# DIGITALS.net
KiCad netlist of a schematic drawn in Altium Designer
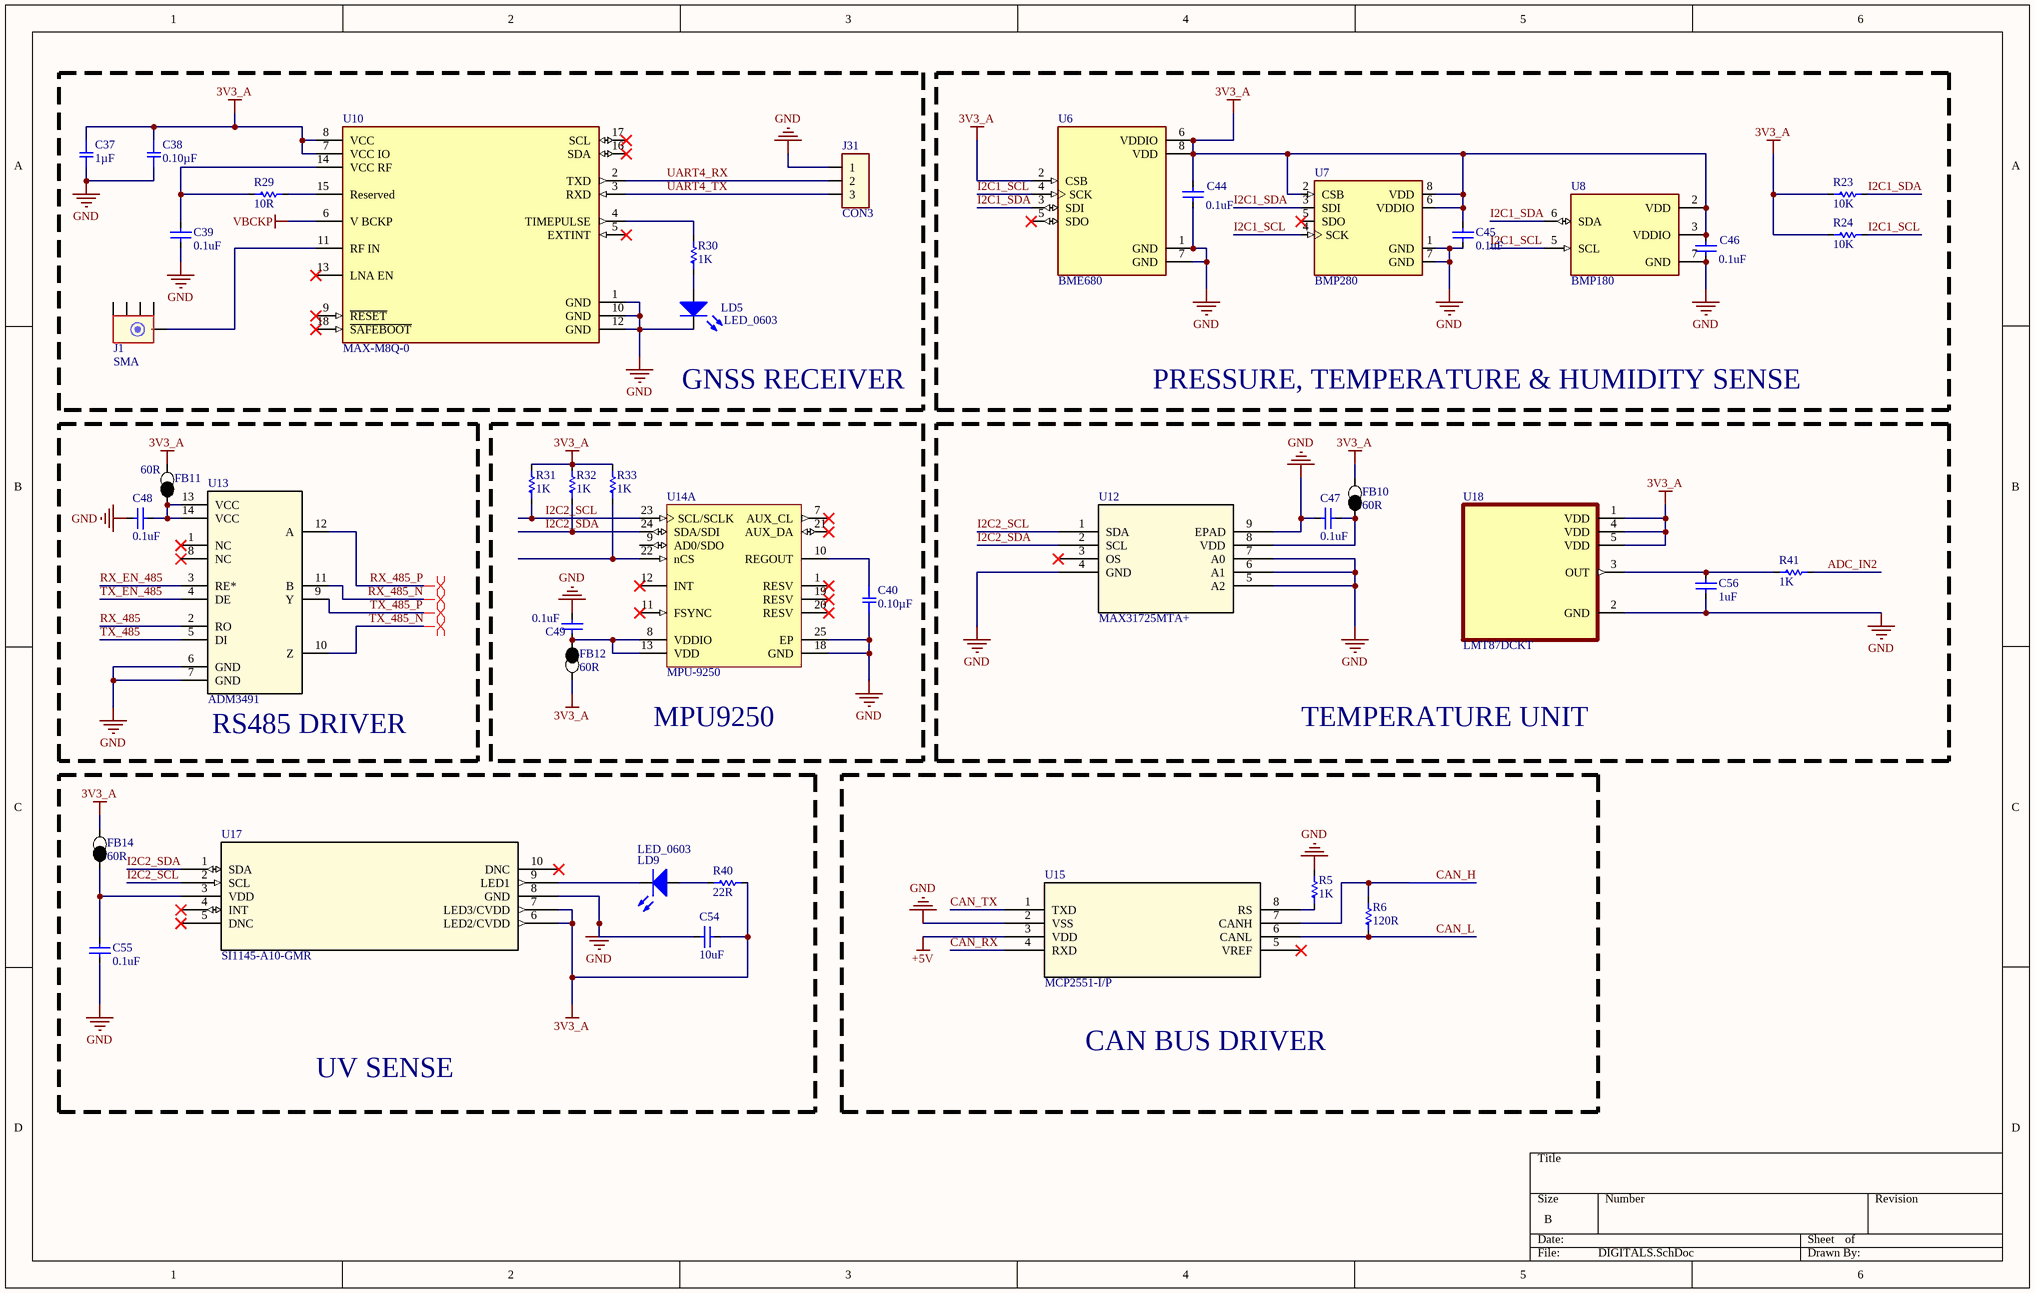
[diagram p0: DIGITALS.SchDoc]

(export (version "E")
  (design (tool "Eeschema 10.0.6"))
  (components
    (comp (ref "C37")
      (value "1µF")
      (footprint "SMD-0603C")
      (description "CAP CER 1UF 25V X5R 0603")
      (fields
        (field (name "DIGI-KEY PART NUMBER") "490-12321-1-ND")
        (field (name "PART NUMBER") "GRT188R61E105KE13D")
      )
      (libsource (lib "capacitor_murata_0603") (part "GRT188R61E105KE13D"))
    )
    (comp (ref "C38")
      (value "0.10µF")
      (footprint "SMD-0603C")
      (description "CAP CER 0.1UF 50V X7R 0603")
      (fields
        (field (name "DIGI-KEY PART NUMBER") "490-5798-1-ND")
        (field (name "PART NUMBER") "GCJ188R71H104KA12D")
      )
      (libsource (lib "capacitor_murata_0603") (part "GCJ188R71H104KA12D"))
    )
    (comp (ref "C39")
      (value "0.1uF")
      (footprint "CAPC1608-0603X90N")
      (description "CAP CER 0.1UF 50V X7R 0603")
      (fields (field (name "MANUFACTURER") "Samsung Electro-Mechanics") (field (name "VOLTAGE") "50V"))
      (libsource (lib "ANTSIS_PASSIVE") (part "CAP 0.1uF"))
    )
    (comp (ref "C40")
      (value "0.10µF")
      (footprint "SMD-0603C")
      (description "CAP CER 0.1UF 16V X7R 0603")
      (fields
        (field (name "DIGI-KEY PART NUMBER") "490-5796-1-ND")
        (field (name "PART NUMBER") "GCJ188R71C104KA01D")
      )
      (libsource (lib "capacitor_murata_0603") (part "GCJ188R71C104KA01D"))
    )
    (comp (ref "C44")
      (value "0.1uF")
      (footprint "CAPC1608-0603X90N")
      (description "CAP CER 0.1UF 50V X7R 0603")
      (fields (field (name "MANUFACTURER") "Samsung Electro-Mechanics") (field (name "VOLTAGE") "50V"))
      (libsource (lib "ANTSIS_PASSIVE") (part "CAP 0.1uF"))
    )
    (comp (ref "C45")
      (value "0.1uF")
      (footprint "CAPC1608-0603X90N")
      (description "CAP CER 0.1UF 50V X7R 0603")
      (fields (field (name "MANUFACTURER") "Samsung Electro-Mechanics") (field (name "VOLTAGE") "50V"))
      (libsource (lib "ANTSIS_PASSIVE") (part "CAP 0.1uF"))
    )
    (comp (ref "C46")
      (value "0.1uF")
      (footprint "CAPC1608-0603X90N")
      (description "CAP CER 0.1UF 50V X7R 0603")
      (fields (field (name "MANUFACTURER") "Samsung Electro-Mechanics") (field (name "VOLTAGE") "50V"))
      (libsource (lib "ANTSIS_PASSIVE") (part "CAP 0.1uF"))
    )
    (comp (ref "C47")
      (value "0.1uF")
      (footprint "CAPC1608-0603X90N")
      (description "CAP CER 0.1UF 50V X7R 0603")
      (fields (field (name "MANUFACTURER") "Samsung Electro-Mechanics") (field (name "VOLTAGE") "50V"))
      (libsource (lib "ANTSIS_PASSIVE") (part "CAP 0.1uF"))
    )
    (comp (ref "C48")
      (value "0.1uF")
      (footprint "CAPC1608-0603X90N")
      (description "CAP CER 0.1UF 50V X7R 0603")
      (fields (field (name "MANUFACTURER") "Samsung Electro-Mechanics") (field (name "VOLTAGE") "50V"))
      (libsource (lib "ANTSIS_PASSIVE") (part "CAP 0.1uF"))
    )
    (comp (ref "C49")
      (value "0.1uF")
      (footprint "CAPC1608-0603X90N")
      (description "CAP CER 0.1UF 50V X7R 0603")
      (fields (field (name "MANUFACTURER") "Samsung Electro-Mechanics") (field (name "VOLTAGE") "50V"))
      (libsource (lib "ANTSIS_PASSIVE") (part "CAP 0.1uF"))
    )
    (comp (ref "C54")
      (value "10uF")
      (footprint "CAPC1608-0603X90N")
      (description "CAP CER 10UF 10V X5R 0603")
      (fields (field (name "MANUFACTURER") "Samsung Electro-Mechanics") (field (name "VOLTAGE") "10V"))
      (libsource (lib "ANTSIS_PASSIVE") (part "CAP 10uF"))
    )
    (comp (ref "C55")
      (value "0.1uF")
      (footprint "CAPC1608-0603X90N")
      (description "CAP CER 0.1UF 50V X7R 0603")
      (fields (field (name "MANUFACTURER") "Samsung Electro-Mechanics") (field (name "VOLTAGE") "50V"))
      (libsource (lib "ANTSIS_PASSIVE") (part "CAP 0.1uF"))
    )
    (comp (ref "C56")
      (value "1uF")
      (footprint "CAPC1608-0603X90N")
      (description "CAP CER 1UF 25V X7R 0603")
      (fields (field (name "MANUFACTURER") "Samsung Electro-Mechanics") (field (name "VOLTAGE") "25V"))
      (libsource (lib "ANTSIS_PASSIVE") (part "CAP 1uF"))
    )
    (comp (ref "FB10")
      (value "60R")
      (footprint "INDC1608-0603X80N")
      (description "FERRITE BEAD 60 OHM 0603 1LN")
      (fields (field (name "MANUFACTURER") "Würth Elektronik") (field (name "TOLERANCE") "-55°C ~ 125°C"))
      (libsource (lib "ANTSIS_PASSIVE") (part "FERRITE 60R 3A"))
    )
    (comp (ref "FB11")
      (value "60R")
      (footprint "INDC1608-0603X80N")
      (description "FERRITE BEAD 60 OHM 0603 1LN")
      (fields (field (name "MANUFACTURER") "Würth Elektronik") (field (name "TOLERANCE") "-55°C ~ 125°C"))
      (libsource (lib "ANTSIS_PASSIVE") (part "FERRITE 60R 3A"))
    )
    (comp (ref "FB12")
      (value "60R")
      (footprint "INDC1608-0603X80N")
      (description "FERRITE BEAD 60 OHM 0603 1LN")
      (fields (field (name "MANUFACTURER") "Würth Elektronik") (field (name "TOLERANCE") "-55°C ~ 125°C"))
      (libsource (lib "ANTSIS_PASSIVE") (part "FERRITE 60R 3A"))
    )
    (comp (ref "FB14")
      (value "60R")
      (footprint "INDC1608-0603X80N")
      (description "FERRITE BEAD 60 OHM 0603 1LN")
      (fields (field (name "MANUFACTURER") "Würth Elektronik") (field (name "TOLERANCE") "-55°C ~ 125°C"))
      (libsource (lib "ANTSIS_PASSIVE") (part "FERRITE 60R 3A"))
    )
    (comp (ref "J1")
      (value "SMA")
      (footprint "HUBER-SUHNER_85 SMA-50-0-101/111 NE")
      (libsource (lib "ANTSIS_CONNECTORS") (part "SMA"))
    )
    (comp (ref "J31")
      (value "CON3")
      (footprint "HDR1X3M")
      (libsource (lib "ANTSIS_CONNECTORS") (part "CON3"))
    )
    (comp (ref "LD5")
      (value "LED_0603")
      (footprint "LED0603-1608X55N-GREEN")
      (description "LED GREEN CLEAR CHIP SMD")
      (fields (field (name "MANUFACTURER") "Lite-On Inc.") (field (name "VOLTAGE") "2.1V"))
      (libsource (lib "ANTSIS_DIODE_TRANSISTOR") (part "LED_0603"))
    )
    (comp (ref "LD9")
      (value "LED_0603")
      (footprint "LED0603-1608X55N-GREEN")
      (description "LED GREEN CLEAR CHIP SMD")
      (fields (field (name "MANUFACTURER") "Lite-On Inc.") (field (name "VOLTAGE") "2.1V"))
      (libsource (lib "ANTSIS_DIODE_TRANSISTOR") (part "LED_0603"))
    )
    (comp (ref "R5")
      (value "1K")
      (footprint "RESC1608-0603X50N")
      (description "RES SMD 10K OHM 1% 1/10W 0603")
      (fields (field (name "MANUFACTURER") "Yageo"))
      (libsource (lib "ANTSIS_PASSIVE") (part "RESISTOR 10K"))
    )
    (comp (ref "R6")
      (value "120R")
      (footprint "RESC1608-0603X50N")
      (description "RES SMD 0 OHM JUMPER 1/10W 0603")
      (fields (field (name "MANUFACTURER") "Yageo"))
      (libsource (lib "ANTSIS_PASSIVE") (part "RESISTOR 0R"))
    )
    (comp (ref "R23")
      (value "10K")
      (footprint "RESC1608-0603X50N")
      (description "RES SMD 10K OHM 1% 1/10W 0603")
      (fields (field (name "MANUFACTURER") "Yageo"))
      (libsource (lib "ANTSIS_PASSIVE") (part "RESISTOR 10K"))
    )
    (comp (ref "R24")
      (value "10K")
      (footprint "RESC1608-0603X50N")
      (description "RES SMD 10K OHM 1% 1/10W 0603")
      (fields (field (name "MANUFACTURER") "Yageo"))
      (libsource (lib "ANTSIS_PASSIVE") (part "RESISTOR 10K"))
    )
    (comp (ref "R29")
      (value "10R")
      (footprint "RESC1608-0603X50N")
      (description "RES SMD 10 OHM 1% 1/10W 0603")
      (fields (field (name "MANUFACTURER") "Yageo"))
      (libsource (lib "ANTSIS_PASSIVE") (part "RESISTOR 10K"))
    )
    (comp (ref "R30")
      (value "1K")
      (footprint "RESC1608-0603X50N")
      (description "RES SMD 1K OHM 1% 1/10W 0603")
      (fields (field (name "MANUFACTURER") "Yageo"))
      (libsource (lib "ANTSIS_PASSIVE") (part "RESISTOR 1K"))
    )
    (comp (ref "R31")
      (value "1K")
      (footprint "RESC1608-0603X50N")
      (description "RES SMD 1K OHM 1% 1/10W 0603")
      (fields (field (name "MANUFACTURER") "Yageo"))
      (libsource (lib "ANTSIS_PASSIVE") (part "RESISTOR 1K"))
    )
    (comp (ref "R32")
      (value "1K")
      (footprint "RESC1608-0603X50N")
      (description "RES SMD 1K OHM 1% 1/10W 0603")
      (fields (field (name "MANUFACTURER") "Yageo"))
      (libsource (lib "ANTSIS_PASSIVE") (part "RESISTOR 1K"))
    )
    (comp (ref "R33")
      (value "1K")
      (footprint "RESC1608-0603X50N")
      (description "RES SMD 1K OHM 1% 1/10W 0603")
      (fields (field (name "MANUFACTURER") "Yageo"))
      (libsource (lib "ANTSIS_PASSIVE") (part "RESISTOR 1K"))
    )
    (comp (ref "R40")
      (value "22R")
      (footprint "RESC1608-0603X50N")
      (description "RES 22 OHM 5% 1/10W 0603")
      (fields (field (name "MANUFACTURER") "Stackpole Electronics Inc") (field (name "TOLERANCE") "5%"))
      (libsource (lib "ANTSIS_PASSIVE") (part "RESISTOR 22R"))
    )
    (comp (ref "R41")
      (value "1K")
      (footprint "RESC1608-0603X50N")
      (description "RES SMD 1K OHM 1% 1/10W 0603")
      (fields (field (name "MANUFACTURER") "Yageo"))
      (libsource (lib "ANTSIS_PASSIVE") (part "RESISTOR 1K"))
    )
    (comp (ref "U6")
      (value "BME680")
      (footprint "PSON80P300X300X100-8N")
      (description "Gas, Humidity, Pressure, Temperature Sensor IÂ²C, SPI Output")
      (fields (field (name "MF") "Bosch Sensortec"))
      (libsource (lib "BME680") (part "BME680"))
    )
    (comp (ref "U7")
      (value "BMP280")
      (footprint "XDCR_BMP280")
      (description "Pressure Sensor 4.35PSI ~ 15.95PSI _30kPa ~ 110kPa_ Absolute 16b 8-SMD")
      (fields (field (name "DIGI-KEY_PART_NUMBER") "828-1064-1-ND") (field (name "MF") "Bosch"))
      (libsource (lib "BMP280") (part "BMP280"))
    )
    (comp (ref "U8")
      (value "BMP180")
      (footprint "BMP180")
      (description "Pressure Sensor 4.35PSI ~ 15.95PSI _30kPa ~ 110kPa_ Absolute 16 ~ 19 b 7-VLGA")
      (fields (field (name "MF") "Bosch Sensortec") (field (name "DIGI-KEY_PART_NUMBER") "828-1027-1-ND"))
      (libsource (lib "BMP180") (part "BMP180"))
    )
    (comp (ref "U10")
      (value "MAX-M8Q-0")
      (footprint "FP-MAX-M8Q-0-MFG")
      (description "RF RCVR GNSS/GPS 1.575GHZ 18LCC")
      (libsource (lib "Altium Content Vault") (part "3a4eaf80b39255b10f8ea21395ff7da"))
    )
    (comp (ref "U12")
      (value "MAX31725MTA+")
      (footprint "SON65P300X300X80-9N")
      (description "No Description Available")
      (fields (field (name "COPYRIGHT") "Copyright (C) 2021 Ultra Librarian. All rights reserved."))
      (libsource (lib "MAX31725MTA&plus_") (part "MAX31725MTA+"))
    )
    (comp (ref "U13")
      (value "ADM3491")
      (footprint "SOIC127P600-14N")
      (description "1/1 Transceiver Full RS422, RS485 14-SOIC")
      (fields (field (name "MANUFACTURER") "Analog Devices Inc.") (field (name "VOLTAGE") "3V ~ 3.6V"))
      (libsource (lib "ANTSIS") (part "ADM3491"))
    )
    (comp (ref "U14")
      (value "MPU-9250")
      (footprint "INSE-QFN-24-1700X1540TP_N")
      (description "9-axis MotionTracking device, 2.4 to 3,6 V, -40 to 85 degC, 24-Pin QFN, RoHS, Tape and Reel")
      (fields (field (name "MANUFACTURER") "InvenSense"))
      (libsource (lib "Altium Content Vault") (part "INSE-MPU-9250-QFN-24"))
    )
    (comp (ref "U15")
      (value "MCP2551-I/P")
      (footprint "PDIP8_300MC_MCH")
      (description "No Description Available")
      (fields (field (name "COPYRIGHT") "Copyright (C) 2021 Ultra Librarian. All rights reserved."))
      (libsource (lib "MCP2551-I&slash_P") (part "MCP2551-I/P"))
    )
    (comp (ref "U17")
      (value "SI1145-A10-GMR")
      (footprint "QFN10_2X2_SIL")
      (description "No Description Available")
      (fields (field (name "COPYRIGHT") "Copyright (C) 2021 Ultra Librarian. All rights reserved."))
      (libsource (lib "SI1145-A10-GMR") (part "SI1145-A10-GMR"))
    )
    (comp (ref "U18")
      (value "LMT87DCKT")
      (footprint "SOT65P210X110-5N")
      (description "2C 2.7V to 5.5V analog output temperature sensor with -13.6 mV/C gain 5-SC70 -50 to 150")
      (fields (field (name "MF") "Texas Instruments"))
      (libsource (lib "LMT87DCKT") (part "LMT87DCKT"))
    )
  )
  (nets
    (net (code "1") (name "+5V") (class "Default")
      (node (ref "U15") (pin "3") (pinfunction "VDD_3") (pintype "passive"))
    )
    (net (code "2") (name "/ADC_IN2") (class "Default")
      (node (ref "R41") (pin "2") (pinfunction "2_2") (pintype "passive"))
    )
    (net (code "3") (name "/CAN_H") (class "Default")
      (node (ref "R6") (pin "2") (pinfunction "2_2") (pintype "passive"))
      (node (ref "U15") (pin "7") (pinfunction "CANH_7") (pintype "passive"))
    )
    (net (code "4") (name "/CAN_L") (class "Default")
      (node (ref "R6") (pin "1") (pinfunction "1_1") (pintype "passive"))
      (node (ref "U15") (pin "6") (pinfunction "CANL_6") (pintype "passive"))
    )
    (net (code "5") (name "/CAN_RX") (class "Default")
      (node (ref "U15") (pin "4") (pinfunction "RXD_4") (pintype "passive"))
    )
    (net (code "6") (name "/CAN_TX") (class "Default")
      (node (ref "U15") (pin "1") (pinfunction "TXD_1") (pintype "passive"))
    )
    (net (code "7") (name "/I2C1_SCL") (class "Default")
      (node (ref "R24") (pin "2") (pinfunction "2_2") (pintype "passive"))
      (node (ref "U6") (pin "4") (pinfunction "SCK_4") (pintype "input"))
      (node (ref "U7") (pin "4") (pinfunction "SCK_4") (pintype "input"))
      (node (ref "U8") (pin "5") (pinfunction "SCL_5") (pintype "input"))
    )
    (net (code "8") (name "/I2C1_SDA") (class "Default")
      (node (ref "R23") (pin "2") (pinfunction "2_2") (pintype "passive"))
      (node (ref "U6") (pin "3") (pinfunction "SDI_3") (pintype "bidirectional"))
      (node (ref "U7") (pin "3") (pinfunction "SDI_3") (pintype "bidirectional"))
      (node (ref "U8") (pin "6") (pinfunction "SDA_6") (pintype "bidirectional"))
    )
    (net (code "9") (name "/I2C2_SCL") (class "Default")
      (node (ref "R31") (pin "1") (pinfunction "1_1") (pintype "passive"))
      (node (ref "U12") (pin "1") (pinfunction "SDA_1") (pintype "passive"))
      (node (ref "U14") (pin "23") (pinfunction "SCL/SCLK_23") (pintype "input"))
      (node (ref "U17") (pin "2") (pinfunction "SCL_2") (pintype "input"))
    )
    (net (code "10") (name "/I2C2_SDA") (class "Default")
      (node (ref "R32") (pin "1") (pinfunction "1_1") (pintype "passive"))
      (node (ref "U12") (pin "2") (pinfunction "SCL_2") (pintype "passive"))
      (node (ref "U14") (pin "24") (pinfunction "SDA/SDI_24") (pintype "bidirectional"))
      (node (ref "U17") (pin "1") (pinfunction "SDA_1") (pintype "bidirectional"))
    )
    (net (code "11") (name "/RX_485") (class "Default")
      (node (ref "U13") (pin "2") (pinfunction "RO_2") (pintype "passive"))
    )
    (net (code "12") (name "/RX_485_N") (class "Default")
      (node (ref "U13") (pin "11") (pinfunction "B_11") (pintype "passive"))
    )
    (net (code "13") (name "/RX_485_P") (class "Default")
      (node (ref "U13") (pin "12") (pinfunction "A_12") (pintype "passive"))
    )
    (net (code "14") (name "/RX_EN_485") (class "Default")
      (node (ref "U13") (pin "3") (pinfunction "RE*_3") (pintype "passive"))
    )
    (net (code "15") (name "/TX_485") (class "Default")
      (node (ref "U13") (pin "5") (pinfunction "DI_5") (pintype "passive"))
    )
    (net (code "16") (name "/TX_485_N") (class "Default")
      (node (ref "U13") (pin "10") (pinfunction "Z_10") (pintype "passive"))
    )
    (net (code "17") (name "/TX_485_P") (class "Default")
      (node (ref "U13") (pin "9") (pinfunction "Y_9") (pintype "passive"))
    )
    (net (code "18") (name "/TX_EN_485") (class "Default")
      (node (ref "U13") (pin "4") (pinfunction "DE_4") (pintype "passive"))
    )
    (net (code "19") (name "/UART4_RX") (class "Default")
      (node (ref "J31") (pin "2") (pinfunction "2_2") (pintype "passive"))
      (node (ref "U10") (pin "2") (pinfunction "TXD_2") (pintype "output"))
    )
    (net (code "20") (name "/UART4_TX") (class "Default")
      (node (ref "J31") (pin "3") (pinfunction "3_3") (pintype "passive"))
      (node (ref "U10") (pin "3") (pinfunction "RXD_3") (pintype "input"))
    )
    (net (code "21") (name "3V3_A") (class "Default")
      (node (ref "C37") (pin "1") (pinfunction "1_1") (pintype "passive"))
      (node (ref "C38") (pin "1") (pinfunction "1_1") (pintype "passive"))
      (node (ref "C44") (pin "2") (pinfunction "2_2") (pintype "passive"))
      (node (ref "C45") (pin "2") (pinfunction "2_2") (pintype "passive"))
      (node (ref "C46") (pin "2") (pinfunction "2_2") (pintype "passive"))
      (node (ref "C54") (pin "1") (pinfunction "1_1") (pintype "passive"))
      (node (ref "FB10") (pin "2") (pinfunction "2_2") (pintype "passive"))
      (node (ref "FB11") (pin "2") (pinfunction "2_2") (pintype "passive"))
      (node (ref "FB12") (pin "2") (pinfunction "2_2") (pintype "passive"))
      (node (ref "FB14") (pin "2") (pinfunction "2_2") (pintype "passive"))
      (node (ref "R23") (pin "1") (pinfunction "1_1") (pintype "passive"))
      (node (ref "R24") (pin "1") (pinfunction "1_1") (pintype "passive"))
      (node (ref "R31") (pin "2") (pinfunction "2_2") (pintype "passive"))
      (node (ref "R32") (pin "2") (pinfunction "2_2") (pintype "passive"))
      (node (ref "R33") (pin "2") (pinfunction "2_2") (pintype "passive"))
      (node (ref "R40") (pin "2") (pinfunction "2_2") (pintype "passive"))
      (node (ref "U10") (pin "7") (pinfunction "VCC_IO_7") (pintype "power_in"))
      (node (ref "U10") (pin "8") (pinfunction "VCC_8") (pintype "power_in"))
      (node (ref "U17") (pin "6") (pinfunction "LED2/CVDD_6") (pintype "output"))
      (node (ref "U17") (pin "7") (pinfunction "LED3/CVDD_7") (pintype "output"))
      (node (ref "U18") (pin "1") (pinfunction "VDD_1") (pintype "power_in"))
      (node (ref "U18") (pin "4") (pinfunction "VDD_4") (pintype "power_in"))
      (node (ref "U18") (pin "5") (pinfunction "VDD_5") (pintype "power_in"))
      (node (ref "U6") (pin "2") (pinfunction "CSB_2") (pintype "input"))
      (node (ref "U6") (pin "6") (pinfunction "VDDIO_6") (pintype "power_in"))
      (node (ref "U6") (pin "8") (pinfunction "VDD_8") (pintype "power_in"))
      (node (ref "U7") (pin "2") (pinfunction "CSB_2") (pintype "input"))
      (node (ref "U7") (pin "6") (pinfunction "VDDIO_6") (pintype "power_in"))
      (node (ref "U7") (pin "8") (pinfunction "VDD_8") (pintype "power_in"))
      (node (ref "U8") (pin "2") (pinfunction "VDD_2") (pintype "power_in"))
      (node (ref "U8") (pin "3") (pinfunction "VDDIO_3") (pintype "power_in"))
    )
    (net (code "22") (name "GND") (class "Default")
      (node (ref "C37") (pin "2") (pinfunction "2_2") (pintype "passive"))
      (node (ref "C38") (pin "2") (pinfunction "2_2") (pintype "passive"))
      (node (ref "C39") (pin "1") (pinfunction "1_1") (pintype "passive"))
      (node (ref "C40") (pin "2") (pinfunction "2_2") (pintype "passive"))
      (node (ref "C44") (pin "1") (pinfunction "1_1") (pintype "passive"))
      (node (ref "C45") (pin "1") (pinfunction "1_1") (pintype "passive"))
      (node (ref "C46") (pin "1") (pinfunction "1_1") (pintype "passive"))
      (node (ref "C47") (pin "2") (pinfunction "2_2") (pintype "passive"))
      (node (ref "C48") (pin "1") (pinfunction "1_1") (pintype "passive"))
      (node (ref "C49") (pin "2") (pinfunction "2_2") (pintype "passive"))
      (node (ref "C54") (pin "2") (pinfunction "2_2") (pintype "passive"))
      (node (ref "C55") (pin "2") (pinfunction "2_2") (pintype "passive"))
      (node (ref "C56") (pin "1") (pinfunction "1_1") (pintype "passive"))
      (node (ref "J31") (pin "1") (pinfunction "1_1") (pintype "passive"))
      (node (ref "LD5") (pin "2") (pinfunction "K_2") (pintype "passive"))
      (node (ref "R5") (pin "2") (pinfunction "2_2") (pintype "passive"))
      (node (ref "U10") (pin "1") (pinfunction "GND_1") (pintype "power_in"))
      (node (ref "U10") (pin "10") (pinfunction "GND_10") (pintype "power_in"))
      (node (ref "U10") (pin "12") (pinfunction "GND_12") (pintype "power_in"))
      (node (ref "U12") (pin "4") (pinfunction "GND_4") (pintype "power_in"))
      (node (ref "U12") (pin "5") (pinfunction "A2_5") (pintype "passive"))
      (node (ref "U12") (pin "6") (pinfunction "A1_6") (pintype "passive"))
      (node (ref "U12") (pin "7") (pinfunction "A0_7") (pintype "passive"))
      (node (ref "U12") (pin "9") (pinfunction "EPAD_9") (pintype "power_in"))
      (node (ref "U13") (pin "6") (pinfunction "GND_6") (pintype "power_in"))
      (node (ref "U13") (pin "7") (pinfunction "GND_7") (pintype "power_in"))
      (node (ref "U14") (pin "18") (pinfunction "GND_18") (pintype "power_in"))
      (node (ref "U14") (pin "25") (pinfunction "EP_25") (pintype "passive"))
      (node (ref "U15") (pin "2") (pinfunction "VSS_2") (pintype "passive"))
      (node (ref "U17") (pin "8") (pinfunction "GND_8") (pintype "power_in"))
      (node (ref "U18") (pin "2") (pinfunction "GND_2") (pintype "power_in"))
      (node (ref "U6") (pin "1") (pinfunction "GND_1") (pintype "power_in"))
      (node (ref "U6") (pin "7") (pinfunction "GND_7") (pintype "power_in"))
      (node (ref "U7") (pin "1") (pinfunction "GND_1") (pintype "power_in"))
      (node (ref "U7") (pin "7") (pinfunction "GND_7") (pintype "power_in"))
      (node (ref "U8") (pin "7") (pinfunction "GND_7") (pintype "power_in"))
    )
    (net (code "23") (name "Net-(C48-Pad2)") (class "Default")
      (node (ref "C48") (pin "2") (pinfunction "2_2") (pintype "passive"))
      (node (ref "FB11") (pin "1") (pinfunction "1_1") (pintype "passive"))
      (node (ref "U13") (pin "13") (pinfunction "VCC_13") (pintype "power_in"))
      (node (ref "U13") (pin "14") (pinfunction "VCC_14") (pintype "power_in"))
    )
    (net (code "24") (name "Net-(LD5-A)") (class "Default")
      (node (ref "LD5") (pin "1") (pinfunction "A_1") (pintype "passive"))
      (node (ref "R30") (pin "1") (pinfunction "1_1") (pintype "passive"))
    )
    (net (code "25") (name "Net-(LD9-A)") (class "Default")
      (node (ref "LD9") (pin "1") (pinfunction "A_1") (pintype "passive"))
      (node (ref "R40") (pin "1") (pinfunction "1_1") (pintype "passive"))
    )
    (net (code "26") (name "Net-(LD9-K)") (class "Default")
      (node (ref "LD9") (pin "2") (pinfunction "K_2") (pintype "passive"))
      (node (ref "U17") (pin "9") (pinfunction "LED1_9") (pintype "output"))
    )
    (net (code "27") (name "Net-(U10-RF_IN)") (class "Default")
      (node (ref "J1") (pin "1") (pintype "passive"))
      (node (ref "U10") (pin "11") (pinfunction "RF_IN_11") (pintype "passive"))
    )
    (net (code "28") (name "Net-(U10-Reserved)") (class "Default")
      (node (ref "R29") (pin "2") (pinfunction "2_2") (pintype "passive"))
      (node (ref "U10") (pin "15") (pinfunction "Reserved_15") (pintype "passive"))
    )
    (net (code "29") (name "Net-(U10-TIMEPULSE)") (class "Default")
      (node (ref "R30") (pin "2") (pinfunction "2_2") (pintype "passive"))
      (node (ref "U10") (pin "4") (pinfunction "TIMEPULSE_4") (pintype "output"))
    )
    (net (code "30") (name "Net-(U10-VCC_RF)") (class "Default")
      (node (ref "C39") (pin "2") (pinfunction "2_2") (pintype "passive"))
      (node (ref "R29") (pin "1") (pinfunction "1_1") (pintype "passive"))
      (node (ref "U10") (pin "14") (pinfunction "VCC_RF_14") (pintype "power_in"))
    )
    (net (code "31") (name "Net-(U12-VDD)") (class "Default")
      (node (ref "C47") (pin "1") (pinfunction "1_1") (pintype "passive"))
      (node (ref "FB10") (pin "1") (pinfunction "1_1") (pintype "passive"))
      (node (ref "U12") (pin "8") (pinfunction "VDD_8") (pintype "power_in"))
    )
    (net (code "32") (name "Net-(U14A-REGOUT)") (class "Default")
      (node (ref "C40") (pin "1") (pinfunction "1_1") (pintype "passive"))
      (node (ref "U14") (pin "10") (pinfunction "REGOUT_10") (pintype "passive"))
    )
    (net (code "33") (name "Net-(U14A-VDD)") (class "Default")
      (node (ref "C49") (pin "1") (pinfunction "1_1") (pintype "passive"))
      (node (ref "FB12") (pin "1") (pinfunction "1_1") (pintype "passive"))
      (node (ref "U14") (pin "13") (pinfunction "VDD_13") (pintype "power_in"))
      (node (ref "U14") (pin "8") (pinfunction "VDDIO_8") (pintype "power_in"))
    )
    (net (code "34") (name "Net-(U14A-nCS)") (class "Default")
      (node (ref "R33") (pin "1") (pinfunction "1_1") (pintype "passive"))
      (node (ref "U14") (pin "22") (pinfunction "nCS_22") (pintype "input"))
    )
    (net (code "35") (name "Net-(U15-RS)") (class "Default")
      (node (ref "R5") (pin "1") (pinfunction "1_1") (pintype "passive"))
      (node (ref "U15") (pin "8") (pinfunction "RS_8") (pintype "passive"))
    )
    (net (code "36") (name "Net-(U17-VDD)") (class "Default")
      (node (ref "C55") (pin "1") (pinfunction "1_1") (pintype "passive"))
      (node (ref "FB14") (pin "1") (pinfunction "1_1") (pintype "passive"))
      (node (ref "U17") (pin "3") (pinfunction "VDD_3") (pintype "power_in"))
    )
    (net (code "37") (name "Net-(U18-OUT)") (class "Default")
      (node (ref "C56") (pin "2") (pinfunction "2_2") (pintype "passive"))
      (node (ref "R41") (pin "1") (pinfunction "1_1") (pintype "passive"))
      (node (ref "U18") (pin "3") (pinfunction "OUT_3") (pintype "output"))
    )
    (net (code "38") (name "VBCKP") (class "Default")
      (node (ref "U10") (pin "6") (pinfunction "V_BCKP_6") (pintype "power_in"))
    )
    (net (code "39") (name "unconnected-(J1-Pad2)") (class "Default")
      (node (ref "J1") (pin "2") (pintype "passive"))
    )
    (net (code "40") (name "unconnected-(J1-Pad3)") (class "Default")
      (node (ref "J1") (pin "3") (pintype "passive"))
    )
    (net (code "41") (name "unconnected-(J1-Pad4)") (class "Default")
      (node (ref "J1") (pin "4") (pintype "passive"))
    )
    (net (code "42") (name "unconnected-(J1-Pad5)") (class "Default")
      (node (ref "J1") (pin "5") (pintype "passive"))
    )
    (net (code "43") (name "unconnected-(U6-SDO-Pad5)") (class "Default")
      (node (ref "U6") (pin "5") (pinfunction "SDO_5") (pintype "bidirectional+no_connect"))
    )
    (net (code "44") (name "unconnected-(U7-SDO-Pad5)") (class "Default")
      (node (ref "U7") (pin "5") (pinfunction "SDO_5") (pintype "bidirectional+no_connect"))
    )
    (net (code "45") (name "unconnected-(U10-EXTINT-Pad5)") (class "Default")
      (node (ref "U10") (pin "5") (pinfunction "EXTINT_5") (pintype "input+no_connect"))
    )
    (net (code "46") (name "unconnected-(U10-LNA_EN-Pad13)") (class "Default")
      (node (ref "U10") (pin "13") (pinfunction "LNA_EN_13") (pintype "passive+no_connect"))
    )
    (net (code "47") (name "unconnected-(U10-SCL-Pad17)") (class "Default")
      (node (ref "U10") (pin "17") (pinfunction "SCL_17") (pintype "bidirectional+no_connect"))
    )
    (net (code "48") (name "unconnected-(U10-SDA-Pad16)") (class "Default")
      (node (ref "U10") (pin "16") (pinfunction "SDA_16") (pintype "bidirectional+no_connect"))
    )
    (net (code "49") (name "unconnected-(U10-~{RESET}-Pad9)") (class "Default")
      (node (ref "U10") (pin "9") (pinfunction "~{RESET}_9") (pintype "input+no_connect"))
    )
    (net (code "50") (name "unconnected-(U10-~{SAFEBOOT}-Pad18)") (class "Default")
      (node (ref "U10") (pin "18") (pinfunction "~{SAFEBOOT}_18") (pintype "input+no_connect"))
    )
    (net (code "51") (name "unconnected-(U12-OS-Pad3)") (class "Default")
      (node (ref "U12") (pin "3") (pinfunction "OS_3") (pintype "passive+no_connect"))
    )
    (net (code "52") (name "unconnected-(U13-NC-Pad1)") (class "Default")
      (node (ref "U13") (pin "1") (pinfunction "NC_1") (pintype "passive+no_connect"))
    )
    (net (code "53") (name "unconnected-(U13-NC-Pad8)") (class "Default")
      (node (ref "U13") (pin "8") (pinfunction "NC_8") (pintype "passive+no_connect"))
    )
    (net (code "54") (name "unconnected-(U14A-AD0{slash}SDO-Pad9)") (class "Default")
      (node (ref "U14") (pin "9") (pinfunction "AD0/SDO_9") (pintype "bidirectional"))
    )
    (net (code "55") (name "unconnected-(U14A-AUX_CL-Pad7)") (class "Default")
      (node (ref "U14") (pin "7") (pinfunction "AUX_CL_7") (pintype "output+no_connect"))
    )
    (net (code "56") (name "unconnected-(U14A-AUX_DA-Pad21)") (class "Default")
      (node (ref "U14") (pin "21") (pinfunction "AUX_DA_21") (pintype "bidirectional+no_connect"))
    )
    (net (code "57") (name "unconnected-(U14A-FSYNC-Pad11)") (class "Default")
      (node (ref "U14") (pin "11") (pinfunction "FSYNC_11") (pintype "input+no_connect"))
    )
    (net (code "58") (name "unconnected-(U14A-INT-Pad12)") (class "Default")
      (node (ref "U14") (pin "12") (pinfunction "INT_12") (pintype "tri_state+no_connect"))
    )
    (net (code "59") (name "unconnected-(U14A-RESV-Pad1)") (class "Default")
      (node (ref "U14") (pin "1") (pinfunction "RESV_1") (pintype "power_in+no_connect"))
    )
    (net (code "60") (name "unconnected-(U14A-RESV-Pad19)") (class "Default")
      (node (ref "U14") (pin "19") (pinfunction "RESV_19") (pintype "passive+no_connect"))
    )
    (net (code "61") (name "unconnected-(U14A-RESV-Pad20)") (class "Default")
      (node (ref "U14") (pin "20") (pinfunction "RESV_20") (pintype "power_in+no_connect"))
    )
    (net (code "62") (name "unconnected-(U15-VREF-Pad5)") (class "Default")
      (node (ref "U15") (pin "5") (pinfunction "VREF_5") (pintype "passive+no_connect"))
    )
    (net (code "63") (name "unconnected-(U17-DNC-Pad5)") (class "Default")
      (node (ref "U17") (pin "5") (pinfunction "DNC_5") (pintype "passive+no_connect"))
    )
    (net (code "64") (name "unconnected-(U17-DNC-Pad10)") (class "Default")
      (node (ref "U17") (pin "10") (pinfunction "DNC_10") (pintype "passive+no_connect"))
    )
    (net (code "65") (name "unconnected-(U17-INT-Pad4)") (class "Default")
      (node (ref "U17") (pin "4") (pinfunction "INT_4") (pintype "bidirectional+no_connect"))
    )
  )
)
